# llrf_afe_fpga_pwr.net
KiCad netlist of a schematic drawn in Altium Designer
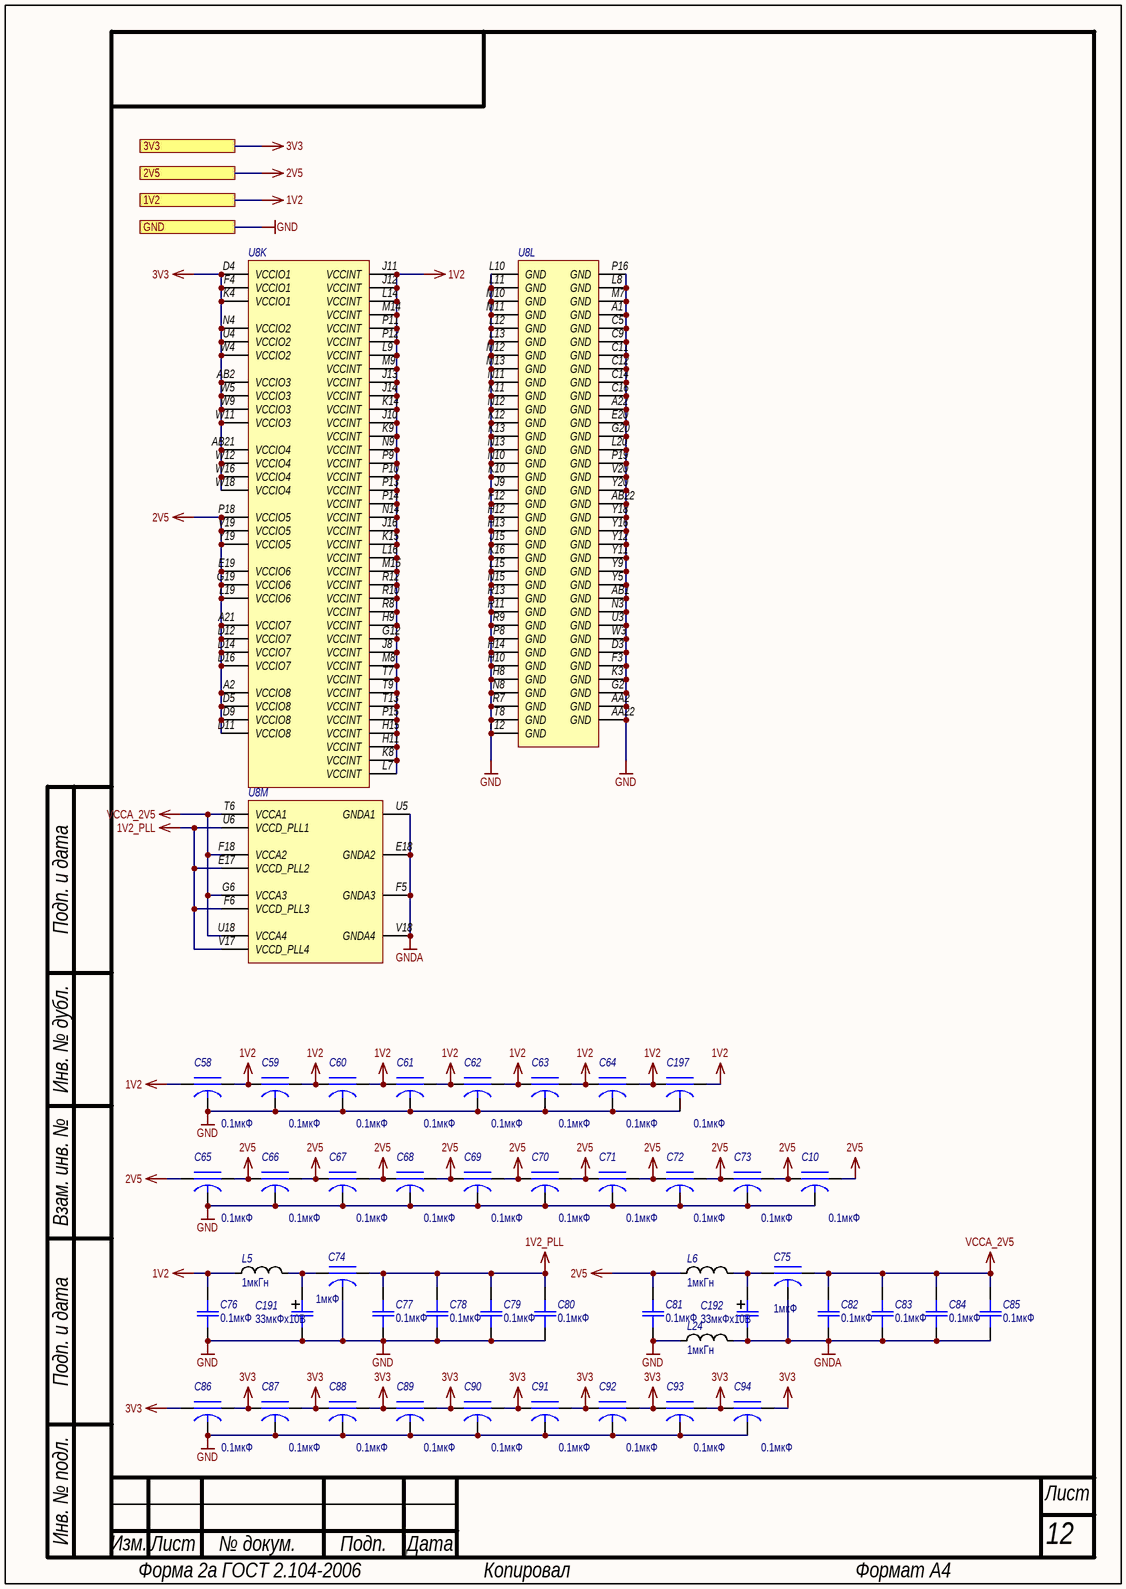
[diagram p0: llrf_afe_fpga_pwr.SchDoc]

(export (version "E")
  (design (tool "Eeschema 10.0.6"))
  (components
    (comp (ref "C10")
      (value "0.1мкФ")
      (footprint "3pol_SMD0402")
      (fields (field (name "Comment") "NFM15PC104D0J3"))
      (libsource (lib "Capacitop_3Pol") (part "Capacitop_3Pol"))
    )
    (comp (ref "C58")
      (value "0.1мкФ")
      (footprint "3pol_SMD0402")
      (fields (field (name "Comment") "NFM15PC104D0J3"))
      (libsource (lib "Capacitop_3Pol") (part "Capacitop_3Pol"))
    )
    (comp (ref "C59")
      (value "0.1мкФ")
      (footprint "3pol_SMD0402")
      (fields (field (name "Comment") "NFM15PC104D0J3"))
      (libsource (lib "Capacitop_3Pol") (part "Capacitop_3Pol"))
    )
    (comp (ref "C60")
      (value "0.1мкФ")
      (footprint "3pol_SMD0402")
      (fields (field (name "Comment") "NFM15PC104D0J3"))
      (libsource (lib "Capacitop_3Pol") (part "Capacitop_3Pol"))
    )
    (comp (ref "C61")
      (value "0.1мкФ")
      (footprint "3pol_SMD0402")
      (fields (field (name "Comment") "NFM15PC104D0J3"))
      (libsource (lib "Capacitop_3Pol") (part "Capacitop_3Pol"))
    )
    (comp (ref "C62")
      (value "0.1мкФ")
      (footprint "3pol_SMD0402")
      (fields (field (name "Comment") "NFM15PC104D0J3"))
      (libsource (lib "Capacitop_3Pol") (part "Capacitop_3Pol"))
    )
    (comp (ref "C63")
      (value "0.1мкФ")
      (footprint "3pol_SMD0402")
      (fields (field (name "Comment") "NFM15PC104D0J3"))
      (libsource (lib "Capacitop_3Pol") (part "Capacitop_3Pol"))
    )
    (comp (ref "C64")
      (value "0.1мкФ")
      (footprint "3pol_SMD0402")
      (fields (field (name "Comment") "NFM15PC104D0J3"))
      (libsource (lib "Capacitop_3Pol") (part "Capacitop_3Pol"))
    )
    (comp (ref "C65")
      (value "0.1мкФ")
      (footprint "3pol_SMD0402")
      (fields (field (name "Comment") "NFM15PC104D0J3"))
      (libsource (lib "Capacitop_3Pol") (part "Capacitop_3Pol"))
    )
    (comp (ref "C66")
      (value "0.1мкФ")
      (footprint "3pol_SMD0402")
      (fields (field (name "Comment") "NFM15PC104D0J3"))
      (libsource (lib "Capacitop_3Pol") (part "Capacitop_3Pol"))
    )
    (comp (ref "C67")
      (value "0.1мкФ")
      (footprint "3pol_SMD0402")
      (fields (field (name "Comment") "NFM15PC104D0J3"))
      (libsource (lib "Capacitop_3Pol") (part "Capacitop_3Pol"))
    )
    (comp (ref "C68")
      (value "0.1мкФ")
      (footprint "3pol_SMD0402")
      (fields (field (name "Comment") "NFM15PC104D0J3"))
      (libsource (lib "Capacitop_3Pol") (part "Capacitop_3Pol"))
    )
    (comp (ref "C69")
      (value "0.1мкФ")
      (footprint "3pol_SMD0402")
      (fields (field (name "Comment") "NFM15PC104D0J3"))
      (libsource (lib "Capacitop_3Pol") (part "Capacitop_3Pol"))
    )
    (comp (ref "C70")
      (value "0.1мкФ")
      (footprint "3pol_SMD0402")
      (fields (field (name "Comment") "NFM15PC104D0J3"))
      (libsource (lib "Capacitop_3Pol") (part "Capacitop_3Pol"))
    )
    (comp (ref "C71")
      (value "0.1мкФ")
      (footprint "3pol_SMD0402")
      (fields (field (name "Comment") "NFM15PC104D0J3"))
      (libsource (lib "Capacitop_3Pol") (part "Capacitop_3Pol"))
    )
    (comp (ref "C72")
      (value "0.1мкФ")
      (footprint "3pol_SMD0402")
      (fields (field (name "Comment") "NFM15PC104D0J3"))
      (libsource (lib "Capacitop_3Pol") (part "Capacitop_3Pol"))
    )
    (comp (ref "C73")
      (value "0.1мкФ")
      (footprint "3pol_SMD0402")
      (fields (field (name "Comment") "NFM15PC104D0J3"))
      (libsource (lib "Capacitop_3Pol") (part "Capacitop_3Pol"))
    )
    (comp (ref "C74")
      (value "1мкФ")
      (footprint "3pol_SMD0402")
      (fields (field (name "Comment") "NFM15PC105D0J3"))
      (libsource (lib "Capacitop_3Pol") (part "Capacitop_3Pol"))
    )
    (comp (ref "C75")
      (value "1мкФ")
      (footprint "3pol_SMD0402")
      (fields (field (name "Comment") "NFM15PC105D0J3"))
      (libsource (lib "Capacitop_3Pol") (part "Capacitop_3Pol"))
    )
    (comp (ref "C76")
      (value "0.1мкФ")
      (footprint "SMD_C0402")
      (description "Capacitor")
      (libsource (lib "Passive") (part "Capacitor"))
    )
    (comp (ref "C77")
      (value "0.1мкФ")
      (footprint "SMD_C0402")
      (description "Capacitor")
      (libsource (lib "Passive") (part "Capacitor"))
    )
    (comp (ref "C78")
      (value "0.1мкФ")
      (footprint "SMD_C0402")
      (description "Capacitor")
      (libsource (lib "Passive") (part "Capacitor"))
    )
    (comp (ref "C79")
      (value "0.1мкФ")
      (footprint "SMD_C0402")
      (description "Capacitor")
      (libsource (lib "Passive") (part "Capacitor"))
    )
    (comp (ref "C80")
      (value "0.1мкФ")
      (footprint "SMD_C0402")
      (description "Capacitor")
      (libsource (lib "Passive") (part "Capacitor"))
    )
    (comp (ref "C81")
      (value "0.1мкФ")
      (footprint "SMD_C0402")
      (description "Capacitor")
      (libsource (lib "Passive") (part "Capacitor"))
    )
    (comp (ref "C82")
      (value "0.1мкФ")
      (footprint "SMD_C0402")
      (description "Capacitor")
      (libsource (lib "Passive") (part "Capacitor"))
    )
    (comp (ref "C83")
      (value "0.1мкФ")
      (footprint "SMD_C0402")
      (description "Capacitor")
      (libsource (lib "Passive") (part "Capacitor"))
    )
    (comp (ref "C84")
      (value "0.1мкФ")
      (footprint "SMD_C0402")
      (description "Capacitor")
      (libsource (lib "Passive") (part "Capacitor"))
    )
    (comp (ref "C85")
      (value "0.1мкФ")
      (footprint "SMD_C0402")
      (description "Capacitor")
      (libsource (lib "Passive") (part "Capacitor"))
    )
    (comp (ref "C86")
      (value "0.1мкФ")
      (footprint "3pol_SMD0402")
      (fields (field (name "Comment") "NFM15PC104D0J3"))
      (libsource (lib "Capacitop_3Pol") (part "Capacitop_3Pol"))
    )
    (comp (ref "C87")
      (value "0.1мкФ")
      (footprint "3pol_SMD0402")
      (fields (field (name "Comment") "NFM15PC104D0J3"))
      (libsource (lib "Capacitop_3Pol") (part "Capacitop_3Pol"))
    )
    (comp (ref "C88")
      (value "0.1мкФ")
      (footprint "3pol_SMD0402")
      (fields (field (name "Comment") "NFM15PC104D0J3"))
      (libsource (lib "Capacitop_3Pol") (part "Capacitop_3Pol"))
    )
    (comp (ref "C89")
      (value "0.1мкФ")
      (footprint "3pol_SMD0402")
      (fields (field (name "Comment") "NFM15PC104D0J3"))
      (libsource (lib "Capacitop_3Pol") (part "Capacitop_3Pol"))
    )
    (comp (ref "C90")
      (value "0.1мкФ")
      (footprint "3pol_SMD0402")
      (fields (field (name "Comment") "NFM15PC104D0J3"))
      (libsource (lib "Capacitop_3Pol") (part "Capacitop_3Pol"))
    )
    (comp (ref "C91")
      (value "0.1мкФ")
      (footprint "3pol_SMD0402")
      (fields (field (name "Comment") "NFM15PC104D0J3"))
      (libsource (lib "Capacitop_3Pol") (part "Capacitop_3Pol"))
    )
    (comp (ref "C92")
      (value "0.1мкФ")
      (footprint "3pol_SMD0402")
      (fields (field (name "Comment") "NFM15PC104D0J3"))
      (libsource (lib "Capacitop_3Pol") (part "Capacitop_3Pol"))
    )
    (comp (ref "C93")
      (value "0.1мкФ")
      (footprint "3pol_SMD0402")
      (fields (field (name "Comment") "NFM15PC104D0J3"))
      (libsource (lib "Capacitop_3Pol") (part "Capacitop_3Pol"))
    )
    (comp (ref "C94")
      (value "0.1мкФ")
      (footprint "3pol_SMD0402")
      (fields (field (name "Comment") "NFM15PC104D0J3"))
      (libsource (lib "Capacitop_3Pol") (part "Capacitop_3Pol"))
    )
    (comp (ref "C191")
      (value "33мкФх10В")
      (footprint "SMD_size_B")
      (description "Polarized capacitor")
      (libsource (lib "Passive") (part "Capacitor_pol"))
    )
    (comp (ref "C192")
      (value "33мкФх10В")
      (footprint "SMD_size_B")
      (description "Polarized capacitor")
      (libsource (lib "Passive") (part "Capacitor_pol"))
    )
    (comp (ref "C197")
      (value "0.1мкФ")
      (footprint "3pol_SMD0402")
      (fields (field (name "Comment") "NFM15PC104D0J3"))
      (libsource (lib "Capacitop_3Pol") (part "Capacitop_3Pol"))
    )
    (comp (ref "L5")
      (value "1мкГн")
      (footprint "SMD_0805")
      (description "Inductor")
      (libsource (lib "Passive") (part "Inductor"))
    )
    (comp (ref "L6")
      (value "1мкГн")
      (footprint "SMD_0805")
      (description "Inductor")
      (libsource (lib "Passive") (part "Inductor"))
    )
    (comp (ref "L24")
      (value "1мкГн")
      (footprint "SMD_0805")
      (description "Inductor")
      (libsource (lib "Passive") (part "Inductor"))
    )
    (comp (ref "U8")
      (value "EP4CE55F23C8")
      (footprint "FBGA484_A-240")
      (fields (field (name "MANUFACTURER") "Altera"))
      (libsource (lib "Altium Content Vault") (part "FPGA-ALEP4C-EP4CE55-F484"))
    )
  )
  (nets
    (net (code "1") (name "1V2") (class "Default")
      (node (ref "C197") (pin "1") (pinfunction "Input_1") (pintype "passive"))
      (node (ref "C197") (pin "3") (pinfunction "Output_3") (pintype "passive"))
      (node (ref "C58") (pin "1") (pinfunction "Input_1") (pintype "passive"))
      (node (ref "C58") (pin "3") (pinfunction "Output_3") (pintype "passive"))
      (node (ref "C59") (pin "1") (pinfunction "Input_1") (pintype "passive"))
      (node (ref "C59") (pin "3") (pinfunction "Output_3") (pintype "passive"))
      (node (ref "C60") (pin "1") (pinfunction "Input_1") (pintype "passive"))
      (node (ref "C60") (pin "3") (pinfunction "Output_3") (pintype "passive"))
      (node (ref "C61") (pin "1") (pinfunction "Input_1") (pintype "passive"))
      (node (ref "C61") (pin "3") (pinfunction "Output_3") (pintype "passive"))
      (node (ref "C62") (pin "1") (pinfunction "Input_1") (pintype "passive"))
      (node (ref "C62") (pin "3") (pinfunction "Output_3") (pintype "passive"))
      (node (ref "C63") (pin "1") (pinfunction "Input_1") (pintype "passive"))
      (node (ref "C63") (pin "3") (pinfunction "Output_3") (pintype "passive"))
      (node (ref "C64") (pin "1") (pinfunction "Input_1") (pintype "passive"))
      (node (ref "C64") (pin "3") (pinfunction "Output_3") (pintype "passive"))
      (node (ref "C76") (pin "2") (pinfunction "2_2") (pintype "passive"))
      (node (ref "L5") (pin "2") (pinfunction "2_2") (pintype "passive"))
      (node (ref "U8") (pin "G12") (pinfunction "VCCINT_G12") (pintype "power_in"))
      (node (ref "U8") (pin "H11") (pinfunction "VCCINT_H11") (pintype "power_in"))
      (node (ref "U8") (pin "H15") (pinfunction "VCCINT_H15") (pintype "power_in"))
      (node (ref "U8") (pin "H9") (pinfunction "VCCINT_H9") (pintype "power_in"))
      (node (ref "U8") (pin "J10") (pinfunction "VCCINT_J10") (pintype "power_in"))
      (node (ref "U8") (pin "J11") (pinfunction "VCCINT_J11") (pintype "power_in"))
      (node (ref "U8") (pin "J12") (pinfunction "VCCINT_J12") (pintype "power_in"))
      (node (ref "U8") (pin "J13") (pinfunction "VCCINT_J13") (pintype "power_in"))
      (node (ref "U8") (pin "J14") (pinfunction "VCCINT_J14") (pintype "power_in"))
      (node (ref "U8") (pin "J16") (pinfunction "VCCINT_J16") (pintype "power_in"))
      (node (ref "U8") (pin "J8") (pinfunction "VCCINT_J8") (pintype "power_in"))
      (node (ref "U8") (pin "K14") (pinfunction "VCCINT_K14") (pintype "power_in"))
      (node (ref "U8") (pin "K15") (pinfunction "VCCINT_K15") (pintype "power_in"))
      (node (ref "U8") (pin "K8") (pinfunction "VCCINT_K8") (pintype "power_in"))
      (node (ref "U8") (pin "K9") (pinfunction "VCCINT_K9") (pintype "power_in"))
      (node (ref "U8") (pin "L14") (pinfunction "VCCINT_L14") (pintype "power_in"))
      (node (ref "U8") (pin "L16") (pinfunction "VCCINT_L16") (pintype "power_in"))
      (node (ref "U8") (pin "L7") (pinfunction "VCCINT_L7") (pintype "power_in"))
      (node (ref "U8") (pin "L9") (pinfunction "VCCINT_L9") (pintype "power_in"))
      (node (ref "U8") (pin "M14") (pinfunction "VCCINT_M14") (pintype "power_in"))
      (node (ref "U8") (pin "M15") (pinfunction "VCCINT_M15") (pintype "power_in"))
      (node (ref "U8") (pin "M8") (pinfunction "VCCINT_M8") (pintype "power_in"))
      (node (ref "U8") (pin "M9") (pinfunction "VCCINT_M9") (pintype "power_in"))
      (node (ref "U8") (pin "N14") (pinfunction "VCCINT_N14") (pintype "power_in"))
      (node (ref "U8") (pin "N9") (pinfunction "VCCINT_N9") (pintype "power_in"))
      (node (ref "U8") (pin "P10") (pinfunction "VCCINT_P10") (pintype "power_in"))
      (node (ref "U8") (pin "P11") (pinfunction "VCCINT_P11") (pintype "power_in"))
      (node (ref "U8") (pin "P12") (pinfunction "VCCINT_P12") (pintype "power_in"))
      (node (ref "U8") (pin "P13") (pinfunction "VCCINT_P13") (pintype "power_in"))
      (node (ref "U8") (pin "P14") (pinfunction "VCCINT_P14") (pintype "power_in"))
      (node (ref "U8") (pin "P15") (pinfunction "VCCINT_P15") (pintype "power_in"))
      (node (ref "U8") (pin "P9") (pinfunction "VCCINT_P9") (pintype "power_in"))
      (node (ref "U8") (pin "R10") (pinfunction "VCCINT_R10") (pintype "power_in"))
      (node (ref "U8") (pin "R12") (pinfunction "VCCINT_R12") (pintype "power_in"))
      (node (ref "U8") (pin "R8") (pinfunction "VCCINT_R8") (pintype "power_in"))
      (node (ref "U8") (pin "T13") (pinfunction "VCCINT_T13") (pintype "power_in"))
      (node (ref "U8") (pin "T7") (pinfunction "VCCINT_T7") (pintype "power_in"))
      (node (ref "U8") (pin "T9") (pinfunction "VCCINT_T9") (pintype "power_in"))
    )
    (net (code "2") (name "1V2_PLL") (class "Default")
      (node (ref "C74") (pin "1") (pinfunction "Input_1") (pintype "passive"))
      (node (ref "C77") (pin "2") (pinfunction "2_2") (pintype "passive"))
      (node (ref "C78") (pin "2") (pinfunction "2_2") (pintype "passive"))
      (node (ref "C79") (pin "2") (pinfunction "2_2") (pintype "passive"))
      (node (ref "C80") (pin "2") (pinfunction "2_2") (pintype "passive"))
      (node (ref "U8") (pin "E17") (pinfunction "VCCD_PLL2_E17") (pintype "power_in"))
      (node (ref "U8") (pin "F6") (pinfunction "VCCD_PLL3_F6") (pintype "power_in"))
      (node (ref "U8") (pin "U6") (pinfunction "VCCD_PLL1_U6") (pintype "power_in"))
      (node (ref "U8") (pin "V17") (pinfunction "VCCD_PLL4_V17") (pintype "power_in"))
    )
    (net (code "3") (name "2V5") (class "Default")
      (node (ref "C10") (pin "1") (pinfunction "Input_1") (pintype "passive"))
      (node (ref "C10") (pin "3") (pinfunction "Output_3") (pintype "passive"))
      (node (ref "C65") (pin "1") (pinfunction "Input_1") (pintype "passive"))
      (node (ref "C65") (pin "3") (pinfunction "Output_3") (pintype "passive"))
      (node (ref "C66") (pin "1") (pinfunction "Input_1") (pintype "passive"))
      (node (ref "C66") (pin "3") (pinfunction "Output_3") (pintype "passive"))
      (node (ref "C67") (pin "1") (pinfunction "Input_1") (pintype "passive"))
      (node (ref "C67") (pin "3") (pinfunction "Output_3") (pintype "passive"))
      (node (ref "C68") (pin "1") (pinfunction "Input_1") (pintype "passive"))
      (node (ref "C68") (pin "3") (pinfunction "Output_3") (pintype "passive"))
      (node (ref "C69") (pin "1") (pinfunction "Input_1") (pintype "passive"))
      (node (ref "C69") (pin "3") (pinfunction "Output_3") (pintype "passive"))
      (node (ref "C70") (pin "1") (pinfunction "Input_1") (pintype "passive"))
      (node (ref "C70") (pin "3") (pinfunction "Output_3") (pintype "passive"))
      (node (ref "C71") (pin "1") (pinfunction "Input_1") (pintype "passive"))
      (node (ref "C71") (pin "3") (pinfunction "Output_3") (pintype "passive"))
      (node (ref "C72") (pin "1") (pinfunction "Input_1") (pintype "passive"))
      (node (ref "C72") (pin "3") (pinfunction "Output_3") (pintype "passive"))
      (node (ref "C73") (pin "1") (pinfunction "Input_1") (pintype "passive"))
      (node (ref "C73") (pin "3") (pinfunction "Output_3") (pintype "passive"))
      (node (ref "C81") (pin "2") (pinfunction "2_2") (pintype "passive"))
      (node (ref "L6") (pin "2") (pinfunction "2_2") (pintype "passive"))
      (node (ref "U8") (pin "A2") (pinfunction "VCCIO8_A2") (pintype "power_in"))
      (node (ref "U8") (pin "A21") (pinfunction "VCCIO7_A21") (pintype "power_in"))
      (node (ref "U8") (pin "D11") (pinfunction "VCCIO8_D11") (pintype "power_in"))
      (node (ref "U8") (pin "D12") (pinfunction "VCCIO7_D12") (pintype "power_in"))
      (node (ref "U8") (pin "D14") (pinfunction "VCCIO7_D14") (pintype "power_in"))
      (node (ref "U8") (pin "D16") (pinfunction "VCCIO7_D16") (pintype "power_in"))
      (node (ref "U8") (pin "D5") (pinfunction "VCCIO8_D5") (pintype "power_in"))
      (node (ref "U8") (pin "D9") (pinfunction "VCCIO8_D9") (pintype "power_in"))
      (node (ref "U8") (pin "E19") (pinfunction "VCCIO6_E19") (pintype "power_in"))
      (node (ref "U8") (pin "G19") (pinfunction "VCCIO6_G19") (pintype "power_in"))
      (node (ref "U8") (pin "L19") (pinfunction "VCCIO6_L19") (pintype "power_in"))
      (node (ref "U8") (pin "P18") (pinfunction "VCCIO5_P18") (pintype "power_in"))
      (node (ref "U8") (pin "V19") (pinfunction "VCCIO5_V19") (pintype "power_in"))
      (node (ref "U8") (pin "Y19") (pinfunction "VCCIO5_Y19") (pintype "power_in"))
    )
    (net (code "4") (name "3V3") (class "Default")
      (node (ref "C86") (pin "1") (pinfunction "Input_1") (pintype "passive"))
      (node (ref "C86") (pin "3") (pinfunction "Output_3") (pintype "passive"))
      (node (ref "C87") (pin "1") (pinfunction "Input_1") (pintype "passive"))
      (node (ref "C87") (pin "3") (pinfunction "Output_3") (pintype "passive"))
      (node (ref "C88") (pin "1") (pinfunction "Input_1") (pintype "passive"))
      (node (ref "C88") (pin "3") (pinfunction "Output_3") (pintype "passive"))
      (node (ref "C89") (pin "1") (pinfunction "Input_1") (pintype "passive"))
      (node (ref "C89") (pin "3") (pinfunction "Output_3") (pintype "passive"))
      (node (ref "C90") (pin "1") (pinfunction "Input_1") (pintype "passive"))
      (node (ref "C90") (pin "3") (pinfunction "Output_3") (pintype "passive"))
      (node (ref "C91") (pin "1") (pinfunction "Input_1") (pintype "passive"))
      (node (ref "C91") (pin "3") (pinfunction "Output_3") (pintype "passive"))
      (node (ref "C92") (pin "1") (pinfunction "Input_1") (pintype "passive"))
      (node (ref "C92") (pin "3") (pinfunction "Output_3") (pintype "passive"))
      (node (ref "C93") (pin "1") (pinfunction "Input_1") (pintype "passive"))
      (node (ref "C93") (pin "3") (pinfunction "Output_3") (pintype "passive"))
      (node (ref "C94") (pin "1") (pinfunction "Input_1") (pintype "passive"))
      (node (ref "C94") (pin "3") (pinfunction "Output_3") (pintype "passive"))
      (node (ref "U8") (pin "AB2") (pinfunction "VCCIO3_AB2") (pintype "power_in"))
      (node (ref "U8") (pin "AB21") (pinfunction "VCCIO4_AB21") (pintype "power_in"))
      (node (ref "U8") (pin "D4") (pinfunction "VCCIO1_D4") (pintype "power_in"))
      (node (ref "U8") (pin "F4") (pinfunction "VCCIO1_F4") (pintype "power_in"))
      (node (ref "U8") (pin "K4") (pinfunction "VCCIO1_K4") (pintype "power_in"))
      (node (ref "U8") (pin "N4") (pinfunction "VCCIO2_N4") (pintype "power_in"))
      (node (ref "U8") (pin "U4") (pinfunction "VCCIO2_U4") (pintype "power_in"))
      (node (ref "U8") (pin "W11") (pinfunction "VCCIO3_W11") (pintype "power_in"))
      (node (ref "U8") (pin "W12") (pinfunction "VCCIO4_W12") (pintype "power_in"))
      (node (ref "U8") (pin "W16") (pinfunction "VCCIO4_W16") (pintype "power_in"))
      (node (ref "U8") (pin "W18") (pinfunction "VCCIO4_W18") (pintype "power_in"))
      (node (ref "U8") (pin "W4") (pinfunction "VCCIO2_W4") (pintype "power_in"))
      (node (ref "U8") (pin "W5") (pinfunction "VCCIO3_W5") (pintype "power_in"))
      (node (ref "U8") (pin "W9") (pinfunction "VCCIO3_W9") (pintype "power_in"))
    )
    (net (code "5") (name "GND") (class "Default")
      (node (ref "C10") (pin "2") (pinfunction "GND_2") (pintype "passive"))
      (node (ref "C191") (pin "2") (pinfunction "2_2") (pintype "passive"))
      (node (ref "C197") (pin "2") (pinfunction "GND_2") (pintype "passive"))
      (node (ref "C58") (pin "2") (pinfunction "GND_2") (pintype "passive"))
      (node (ref "C59") (pin "2") (pinfunction "GND_2") (pintype "passive"))
      (node (ref "C60") (pin "2") (pinfunction "GND_2") (pintype "passive"))
      (node (ref "C61") (pin "2") (pinfunction "GND_2") (pintype "passive"))
      (node (ref "C62") (pin "2") (pinfunction "GND_2") (pintype "passive"))
      (node (ref "C63") (pin "2") (pinfunction "GND_2") (pintype "passive"))
      (node (ref "C64") (pin "2") (pinfunction "GND_2") (pintype "passive"))
      (node (ref "C65") (pin "2") (pinfunction "GND_2") (pintype "passive"))
      (node (ref "C66") (pin "2") (pinfunction "GND_2") (pintype "passive"))
      (node (ref "C67") (pin "2") (pinfunction "GND_2") (pintype "passive"))
      (node (ref "C68") (pin "2") (pinfunction "GND_2") (pintype "passive"))
      (node (ref "C69") (pin "2") (pinfunction "GND_2") (pintype "passive"))
      (node (ref "C70") (pin "2") (pinfunction "GND_2") (pintype "passive"))
      (node (ref "C71") (pin "2") (pinfunction "GND_2") (pintype "passive"))
      (node (ref "C72") (pin "2") (pinfunction "GND_2") (pintype "passive"))
      (node (ref "C73") (pin "2") (pinfunction "GND_2") (pintype "passive"))
      (node (ref "C74") (pin "2") (pinfunction "GND_2") (pintype "passive"))
      (node (ref "C76") (pin "1") (pinfunction "1_1") (pintype "passive"))
      (node (ref "C77") (pin "1") (pinfunction "1_1") (pintype "passive"))
      (node (ref "C78") (pin "1") (pinfunction "1_1") (pintype "passive"))
      (node (ref "C79") (pin "1") (pinfunction "1_1") (pintype "passive"))
      (node (ref "C80") (pin "1") (pinfunction "1_1") (pintype "passive"))
      (node (ref "C81") (pin "1") (pinfunction "1_1") (pintype "passive"))
      (node (ref "C86") (pin "2") (pinfunction "GND_2") (pintype "passive"))
      (node (ref "C87") (pin "2") (pinfunction "GND_2") (pintype "passive"))
      (node (ref "C88") (pin "2") (pinfunction "GND_2") (pintype "passive"))
      (node (ref "C89") (pin "2") (pinfunction "GND_2") (pintype "passive"))
      (node (ref "C90") (pin "2") (pinfunction "GND_2") (pintype "passive"))
      (node (ref "C91") (pin "2") (pinfunction "GND_2") (pintype "passive"))
      (node (ref "C92") (pin "2") (pinfunction "GND_2") (pintype "passive"))
      (node (ref "C93") (pin "2") (pinfunction "GND_2") (pintype "passive"))
      (node (ref "C94") (pin "2") (pinfunction "GND_2") (pintype "passive"))
      (node (ref "L24") (pin "2") (pinfunction "2_2") (pintype "passive"))
      (node (ref "U8") (pin "A1") (pinfunction "GND_A1") (pintype "power_in"))
      (node (ref "U8") (pin "A22") (pinfunction "GND_A22") (pintype "power_in"))
      (node (ref "U8") (pin "AA2") (pinfunction "GND_AA2") (pintype "power_in"))
      (node (ref "U8") (pin "AA22") (pinfunction "GND_AA22") (pintype "power_in"))
      (node (ref "U8") (pin "AB1") (pinfunction "GND_AB1") (pintype "power_in"))
      (node (ref "U8") (pin "AB22") (pinfunction "GND_AB22") (pintype "power_in"))
      (node (ref "U8") (pin "C11") (pinfunction "GND_C11") (pintype "power_in"))
      (node (ref "U8") (pin "C12") (pinfunction "GND_C12") (pintype "power_in"))
      (node (ref "U8") (pin "C14") (pinfunction "GND_C14") (pintype "power_in"))
      (node (ref "U8") (pin "C16") (pinfunction "GND_C16") (pintype "power_in"))
      (node (ref "U8") (pin "C5") (pinfunction "GND_C5") (pintype "power_in"))
      (node (ref "U8") (pin "C9") (pinfunction "GND_C9") (pintype "power_in"))
      (node (ref "U8") (pin "D3") (pinfunction "GND_D3") (pintype "power_in"))
      (node (ref "U8") (pin "E20") (pinfunction "GND_E20") (pintype "power_in"))
      (node (ref "U8") (pin "F12") (pinfunction "GND_F12") (pintype "power_in"))
      (node (ref "U8") (pin "F3") (pinfunction "GND_F3") (pintype "power_in"))
      (node (ref "U8") (pin "G2") (pinfunction "GND_G2") (pintype "power_in"))
      (node (ref "U8") (pin "G20") (pinfunction "GND_G20") (pintype "power_in"))
      (node (ref "U8") (pin "H10") (pinfunction "GND_H10") (pintype "power_in"))
      (node (ref "U8") (pin "H12") (pinfunction "GND_H12") (pintype "power_in"))
      (node (ref "U8") (pin "H13") (pinfunction "GND_H13") (pintype "power_in"))
      (node (ref "U8") (pin "H14") (pinfunction "GND_H14") (pintype "power_in"))
      (node (ref "U8") (pin "H8") (pinfunction "GND_H8") (pintype "power_in"))
      (node (ref "U8") (pin "J15") (pinfunction "GND_J15") (pintype "power_in"))
      (node (ref "U8") (pin "J9") (pinfunction "GND_J9") (pintype "power_in"))
      (node (ref "U8") (pin "K10") (pinfunction "GND_K10") (pintype "power_in"))
      (node (ref "U8") (pin "K11") (pinfunction "GND_K11") (pintype "power_in"))
      (node (ref "U8") (pin "K12") (pinfunction "GND_K12") (pintype "power_in"))
      (node (ref "U8") (pin "K13") (pinfunction "GND_K13") (pintype "power_in"))
      (node (ref "U8") (pin "K16") (pinfunction "GND_K16") (pintype "power_in"))
      (node (ref "U8") (pin "K3") (pinfunction "GND_K3") (pintype "power_in"))
      (node (ref "U8") (pin "L10") (pinfunction "GND_L10") (pintype "power_in"))
      (node (ref "U8") (pin "L11") (pinfunction "GND_L11") (pintype "power_in"))
      (node (ref "U8") (pin "L12") (pinfunction "GND_L12") (pintype "power_in"))
      (node (ref "U8") (pin "L13") (pinfunction "GND_L13") (pintype "power_in"))
      (node (ref "U8") (pin "L15") (pinfunction "GND_L15") (pintype "power_in"))
      (node (ref "U8") (pin "L20") (pinfunction "GND_L20") (pintype "power_in"))
      (node (ref "U8") (pin "L8") (pinfunction "GND_L8") (pintype "power_in"))
      (node (ref "U8") (pin "M10") (pinfunction "GND_M10") (pintype "power_in"))
      (node (ref "U8") (pin "M11") (pinfunction "GND_M11") (pintype "power_in"))
      (node (ref "U8") (pin "M12") (pinfunction "GND_M12") (pintype "power_in"))
      (node (ref "U8") (pin "M13") (pinfunction "GND_M13") (pintype "power_in"))
      (node (ref "U8") (pin "M7") (pinfunction "GND_M7") (pintype "power_in"))
      (node (ref "U8") (pin "N10") (pinfunction "GND_N10") (pintype "power_in"))
      (node (ref "U8") (pin "N11") (pinfunction "GND_N11") (pintype "power_in"))
      (node (ref "U8") (pin "N12") (pinfunction "GND_N12") (pintype "power_in"))
      (node (ref "U8") (pin "N13") (pinfunction "GND_N13") (pintype "power_in"))
      (node (ref "U8") (pin "N15") (pinfunction "GND_N15") (pintype "power_in"))
      (node (ref "U8") (pin "N3") (pinfunction "GND_N3") (pintype "power_in"))
      (node (ref "U8") (pin "N8") (pinfunction "GND_N8") (pintype "power_in"))
      (node (ref "U8") (pin "P16") (pinfunction "GND_P16") (pintype "power_in"))
      (node (ref "U8") (pin "P19") (pinfunction "GND_P19") (pintype "power_in"))
      (node (ref "U8") (pin "P8") (pinfunction "GND_P8") (pintype "power_in"))
      (node (ref "U8") (pin "R11") (pinfunction "GND_R11") (pintype "power_in"))
      (node (ref "U8") (pin "R13") (pinfunction "GND_R13") (pintype "power_in"))
      (node (ref "U8") (pin "R7") (pinfunction "GND_R7") (pintype "power_in"))
      (node (ref "U8") (pin "R9") (pinfunction "GND_R9") (pintype "power_in"))
      (node (ref "U8") (pin "T12") (pinfunction "GND_T12") (pintype "power_in"))
      (node (ref "U8") (pin "T8") (pinfunction "GND_T8") (pintype "power_in"))
      (node (ref "U8") (pin "U3") (pinfunction "GND_U3") (pintype "power_in"))
      (node (ref "U8") (pin "V20") (pinfunction "GND_V20") (pintype "power_in"))
      (node (ref "U8") (pin "W3") (pinfunction "GND_W3") (pintype "power_in"))
      (node (ref "U8") (pin "Y11") (pinfunction "GND_Y11") (pintype "power_in"))
      (node (ref "U8") (pin "Y12") (pinfunction "GND_Y12") (pintype "power_in"))
      (node (ref "U8") (pin "Y16") (pinfunction "GND_Y16") (pintype "power_in"))
      (node (ref "U8") (pin "Y18") (pinfunction "GND_Y18") (pintype "power_in"))
      (node (ref "U8") (pin "Y20") (pinfunction "GND_Y20") (pintype "power_in"))
      (node (ref "U8") (pin "Y5") (pinfunction "GND_Y5") (pintype "power_in"))
      (node (ref "U8") (pin "Y9") (pinfunction "GND_Y9") (pintype "power_in"))
    )
    (net (code "6") (name "GNDA") (class "Default")
      (node (ref "C192") (pin "2") (pinfunction "2_2") (pintype "passive"))
      (node (ref "C75") (pin "2") (pinfunction "GND_2") (pintype "passive"))
      (node (ref "C82") (pin "1") (pinfunction "1_1") (pintype "passive"))
      (node (ref "C83") (pin "1") (pinfunction "1_1") (pintype "passive"))
      (node (ref "C84") (pin "1") (pinfunction "1_1") (pintype "passive"))
      (node (ref "C85") (pin "1") (pinfunction "1_1") (pintype "passive"))
      (node (ref "L24") (pin "1") (pinfunction "1_1") (pintype "passive"))
      (node (ref "U8") (pin "E18") (pinfunction "GNDA2_E18") (pintype "power_in"))
      (node (ref "U8") (pin "F5") (pinfunction "GNDA3_F5") (pintype "power_in"))
      (node (ref "U8") (pin "U5") (pinfunction "GNDA1_U5") (pintype "power_in"))
      (node (ref "U8") (pin "V18") (pinfunction "GNDA4_V18") (pintype "power_in"))
    )
    (net (code "7") (name "Net-(C74-Output)") (class "Default")
      (node (ref "C191") (pin "1") (pinfunction "1_1") (pintype "passive"))
      (node (ref "C74") (pin "3") (pinfunction "Output_3") (pintype "passive"))
      (node (ref "L5") (pin "1") (pinfunction "1_1") (pintype "passive"))
    )
    (net (code "8") (name "Net-(C75-Output)") (class "Default")
      (node (ref "C192") (pin "1") (pinfunction "1_1") (pintype "passive"))
      (node (ref "C75") (pin "3") (pinfunction "Output_3") (pintype "passive"))
      (node (ref "L6") (pin "1") (pinfunction "1_1") (pintype "passive"))
    )
    (net (code "9") (name "VCCA_2V5") (class "Default")
      (node (ref "C75") (pin "1") (pinfunction "Input_1") (pintype "passive"))
      (node (ref "C82") (pin "2") (pinfunction "2_2") (pintype "passive"))
      (node (ref "C83") (pin "2") (pinfunction "2_2") (pintype "passive"))
      (node (ref "C84") (pin "2") (pinfunction "2_2") (pintype "passive"))
      (node (ref "C85") (pin "2") (pinfunction "2_2") (pintype "passive"))
      (node (ref "U8") (pin "F18") (pinfunction "VCCA2_F18") (pintype "power_in"))
      (node (ref "U8") (pin "G6") (pinfunction "VCCA3_G6") (pintype "power_in"))
      (node (ref "U8") (pin "T6") (pinfunction "VCCA1_T6") (pintype "power_in"))
      (node (ref "U8") (pin "U18") (pinfunction "VCCA4_U18") (pintype "power_in"))
    )
  )
)
